# Ethernet_Interface.net
KiCad netlist of a schematic drawn in Altium Designer
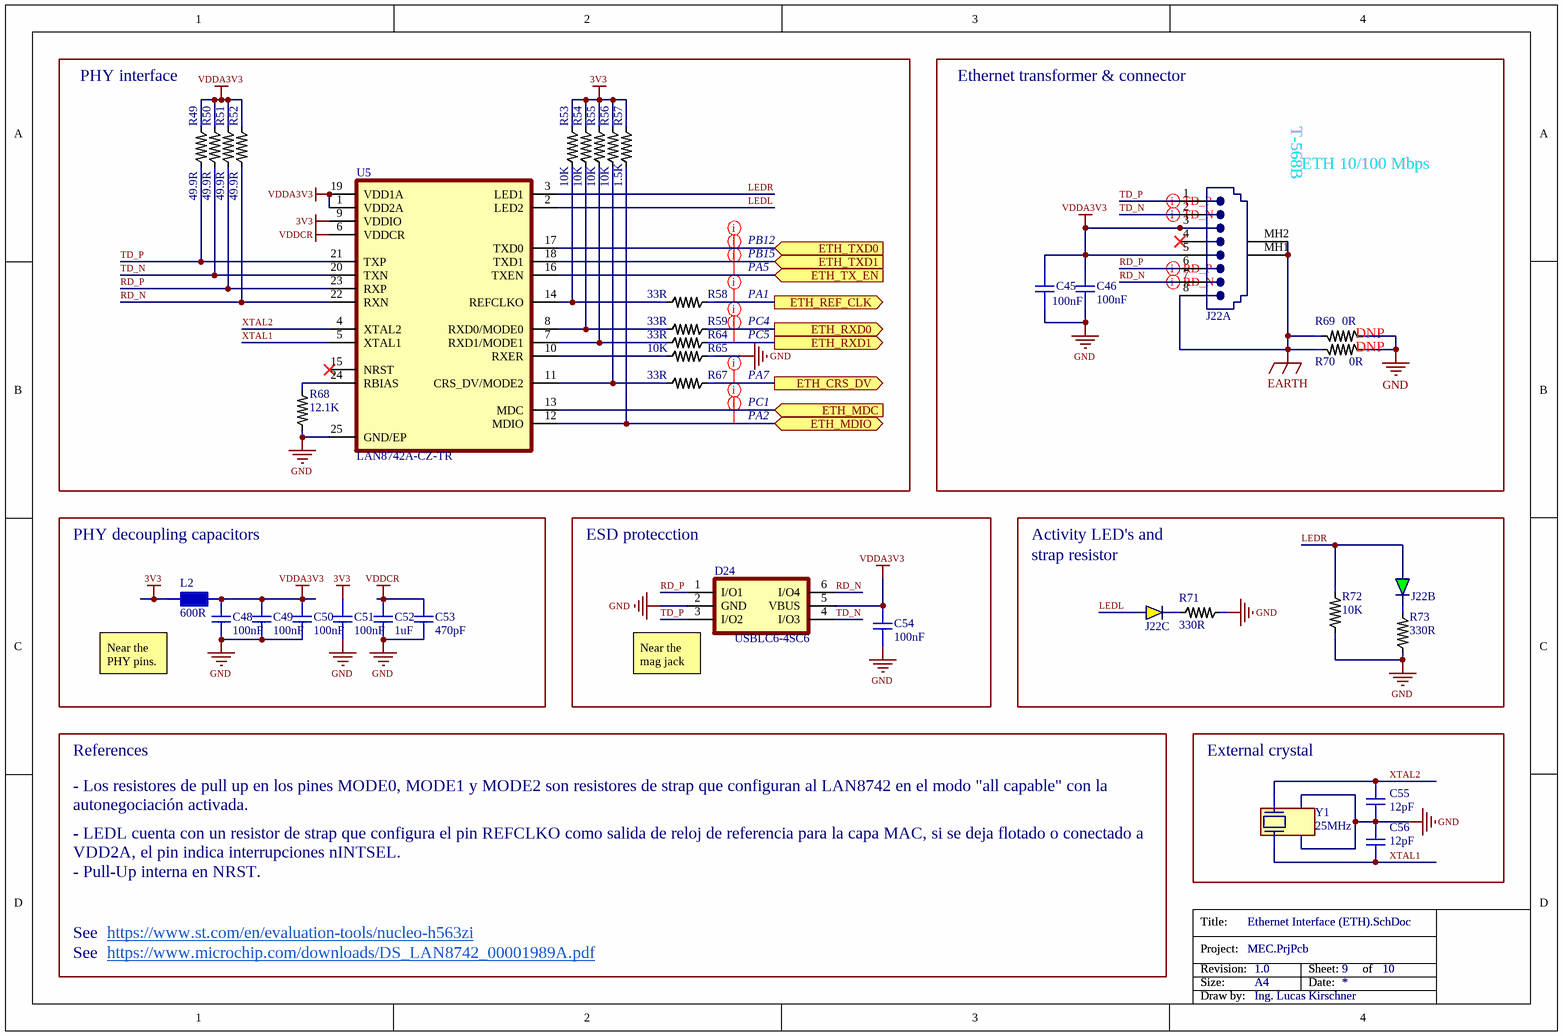
[diagram p0: Ethernet Interface (ETH).SchDoc]

(export (version "E")
  (design (tool "Eeschema 10.0.6"))
  (components
    (comp (ref "C45")
      (value "100nF")
      (footprint "CAPC1005N")
      (description "Multilayer Ceramic Capacitors MLCC - SMD/SMT 50 V 0.1uF X7R 0402 10%")
      (fields (field (name "PART NUMBER") "CC0402KRX5R9BB104") (field (name "MANUFACTURER") "YAGEO"))
      (libsource (lib "SchLib") (part "C-MLCC-100nF-50V-10%-0402"))
    )
    (comp (ref "C46")
      (value "100nF")
      (footprint "CAPC1005N")
      (description "Multilayer Ceramic Capacitors MLCC - SMD/SMT 50 V 0.1uF X7R 0402 10%")
      (fields (field (name "PART NUMBER") "CC0402KRX5R9BB104") (field (name "MANUFACTURER") "YAGEO"))
      (libsource (lib "SchLib") (part "C-MLCC-100nF-50V-10%-0402"))
    )
    (comp (ref "C48")
      (value "100nF")
      (footprint "CAPC1005N")
      (description "Multilayer Ceramic Capacitors MLCC - SMD/SMT 50 V 0.1uF X7R 0402 10%")
      (fields (field (name "PART NUMBER") "CC0402KRX5R9BB104") (field (name "MANUFACTURER") "YAGEO"))
      (libsource (lib "SchLib") (part "C-MLCC-100nF-50V-10%-0402"))
    )
    (comp (ref "C49")
      (value "100nF")
      (footprint "CAPC1005N")
      (description "Multilayer Ceramic Capacitors MLCC - SMD/SMT 50 V 0.1uF X7R 0402 10%")
      (fields (field (name "PART NUMBER") "CC0402KRX5R9BB104") (field (name "MANUFACTURER") "YAGEO"))
      (libsource (lib "SchLib") (part "C-MLCC-100nF-50V-10%-0402"))
    )
    (comp (ref "C50")
      (value "100nF")
      (footprint "CAPC1005N")
      (description "Multilayer Ceramic Capacitors MLCC - SMD/SMT 50 V 0.1uF X7R 0402 10%")
      (fields (field (name "PART NUMBER") "CC0402KRX5R9BB104") (field (name "MANUFACTURER") "YAGEO"))
      (libsource (lib "SchLib") (part "C-MLCC-100nF-50V-10%-0402"))
    )
    (comp (ref "C51")
      (value "100nF")
      (footprint "CAPC1005N")
      (description "Multilayer Ceramic Capacitors MLCC - SMD/SMT 50 V 0.1uF X7R 0402 10%")
      (fields (field (name "PART NUMBER") "CC0402KRX5R9BB104") (field (name "MANUFACTURER") "YAGEO"))
      (libsource (lib "SchLib") (part "C-MLCC-100nF-50V-10%-0402"))
    )
    (comp (ref "C52")
      (value "1uF")
      (footprint "CAPC1005N")
      (description "Multilayer Ceramic Capacitors MLCC - SMD/SMT 50V 1uF X5R 0402 10% HI CV")
      (fields (field (name "PART NUMBER") "CC0402KRX5R9BB105") (field (name "MANUFACTURER") "YAGEO"))
      (libsource (lib "SchLib") (part "C-MLCC-1uF-50V-10%-0402"))
    )
    (comp (ref "C53")
      (value "470pF")
      (footprint "CAPC1005N")
      (description "Multilayer Ceramic Capacitors MLCC - SMD/SMT 50 V 470pF X7R 0402 10%")
      (fields (field (name "PART NUMBER") "CC0402KRX7R9BB471") (field (name "MANUFACTURER") "YAGEO"))
      (libsource (lib "SchLib") (part "C-MLCC-470pF-50V-10%-0402"))
    )
    (comp (ref "C54")
      (value "100nF")
      (footprint "CAPC1005N")
      (description "Multilayer Ceramic Capacitors MLCC - SMD/SMT 50 V 0.1uF X7R 0402 10%")
      (fields (field (name "PART NUMBER") "CC0402KRX5R9BB104") (field (name "MANUFACTURER") "YAGEO"))
      (libsource (lib "SchLib") (part "C-MLCC-100nF-50V-10%-0402"))
    )
    (comp (ref "C55")
      (value "12pF")
      (footprint "CAPC1005N")
      (description "Multilayer Ceramic Capacitors MLCC - SMD/SMT 50 V 12 pF C0G 0402 1%")
      (fields (field (name "PART NUMBER") "CC0402FRNPO9BN120") (field (name "MANUFACTURER") "YAGEO"))
      (libsource (lib "SchLib") (part "C-MLCC-12pF-50V-10%-0402"))
    )
    (comp (ref "C56")
      (value "12pF")
      (footprint "CAPC1005N")
      (description "Multilayer Ceramic Capacitors MLCC - SMD/SMT 50 V 12 pF C0G 0402 1%")
      (fields (field (name "PART NUMBER") "CC0402FRNPO9BN120") (field (name "MANUFACTURER") "YAGEO"))
      (libsource (lib "SchLib") (part "C-MLCC-12pF-50V-10%-0402"))
    )
    (comp (ref "D24")
      (value "ESD Protection Diodes")
      (footprint "SOT95P280X145-6N")
      (description "ESD Protection Diodes / TVS Diodes Low Cap ESD Protect")
      (fields
        (field (name "MANUFACTURER") "STMicroelectronics")
        (field (name "MOUSER PART #") "511-USBLC6-4SC6")
        (field (name "PART NUMBER") "USBLC6-4SC6")
      )
      (libsource (lib "SchLib") (part "D-USBLC6-4SC6"))
    )
    (comp (ref "J22")
      (value "Magnetic Jack Ethernet")
      (footprint "RJ45-8P8C-VERT-THT-MAGJACK")
      (description "Modular Ethernet Connector Jack (Female) 1x1 Shielded Through Hole With LEDs With Magnetics")
      (fields (field (name "MANUFACTURER") "HANRUN") (field (name "PART NUMBER") "HY951180A"))
      (libsource (lib "") (part "J-RJ45-1P-VERT-MAGJACK-SH-LED-THT_1"))
    )
    (comp (ref "L2")
      (value "600R")
      (footprint "INDC1005N")
      (description "Ferrite Beads 600 OHM 25% Alternate Sizing Guide Below")
      (fields
        (field (name "MANUFACTURER") "Murata Electronics")
        (field (name "MOUSER PART #") "81-BLM15AX601SN1D")
      )
      (libsource (lib "SchLib") (part "L-FB-600R-100MHz-500mA-0402"))
    )
    (comp (ref "R49")
      (value "49.9R")
      (footprint "RESC1005N")
      (description "Thick Film Resistors - SMD General Purpose Chip Resistor 0402, 49.9Ohms, 1%, 1/16W")
      (fields (field (name "PART NUMBER") "RC0402FR-0749R9L") (field (name "MANUFACTURER") "YAGEO"))
      (libsource (lib "SchLib") (part "R-THICK-49R9-62.5mW-1%-0402"))
    )
    (comp (ref "R50")
      (value "49.9R")
      (footprint "RESC1005N")
      (description "Thick Film Resistors - SMD General Purpose Chip Resistor 0402, 49.9Ohms, 1%, 1/16W")
      (fields (field (name "PART NUMBER") "RC0402FR-0749R9L") (field (name "MANUFACTURER") "YAGEO"))
      (libsource (lib "SchLib") (part "R-THICK-49R9-62.5mW-1%-0402"))
    )
    (comp (ref "R51")
      (value "49.9R")
      (footprint "RESC1005N")
      (description "Thick Film Resistors - SMD General Purpose Chip Resistor 0402, 49.9Ohms, 1%, 1/16W")
      (fields (field (name "PART NUMBER") "RC0402FR-0749R9L") (field (name "MANUFACTURER") "YAGEO"))
      (libsource (lib "SchLib") (part "R-THICK-49R9-62.5mW-1%-0402"))
    )
    (comp (ref "R52")
      (value "49.9R")
      (footprint "RESC1005N")
      (description "Thick Film Resistors - SMD General Purpose Chip Resistor 0402, 49.9Ohms, 1%, 1/16W")
      (fields (field (name "PART NUMBER") "RC0402FR-0749R9L") (field (name "MANUFACTURER") "YAGEO"))
      (libsource (lib "SchLib") (part "R-THICK-49R9-62.5mW-1%-0402"))
    )
    (comp (ref "R53")
      (value "10K")
      (footprint "RESC1005N")
      (description "Thick Film Resistors - SMD General Purpose Chip Resistor 0402, 10kOhms, 1%, 1/16W")
      (fields (field (name "PART NUMBER") "RC0402FR-0710KL") (field (name "MANUFACTURER") "YAGEO"))
      (libsource (lib "SchLib") (part "R-THICK-10K-62.5mW-1%-0402"))
    )
    (comp (ref "R54")
      (value "10K")
      (footprint "RESC1005N")
      (description "Thick Film Resistors - SMD General Purpose Chip Resistor 0402, 10kOhms, 1%, 1/16W")
      (fields (field (name "PART NUMBER") "RC0402FR-0710KL") (field (name "MANUFACTURER") "YAGEO"))
      (libsource (lib "SchLib") (part "R-THICK-10K-62.5mW-1%-0402"))
    )
    (comp (ref "R55")
      (value "10K")
      (footprint "RESC1005N")
      (description "Thick Film Resistors - SMD General Purpose Chip Resistor 0402, 10kOhms, 1%, 1/16W")
      (fields (field (name "PART NUMBER") "RC0402FR-0710KL") (field (name "MANUFACTURER") "YAGEO"))
      (libsource (lib "SchLib") (part "R-THICK-10K-62.5mW-1%-0402"))
    )
    (comp (ref "R56")
      (value "10K")
      (footprint "RESC1005N")
      (description "Thick Film Resistors - SMD General Purpose Chip Resistor 0402, 10kOhms, 1%, 1/16W")
      (fields (field (name "PART NUMBER") "RC0402FR-0710KL") (field (name "MANUFACTURER") "YAGEO"))
      (libsource (lib "SchLib") (part "R-THICK-10K-62.5mW-1%-0402"))
    )
    (comp (ref "R57")
      (value "1.5K")
      (footprint "RESC1005N")
      (description "Thick Film Resistors - SMD General Purpose Chip Resistor 0402, 1.5kOhms, 1%, 1/16W")
      (fields (field (name "PART NUMBER") "RC0402FR-071K5L") (field (name "MANUFACTURER") "YAGEO"))
      (libsource (lib "SchLib") (part "R-THICK-1K5-62.5mW-1%-0402"))
    )
    (comp (ref "R58")
      (value "33R")
      (footprint "RESC1005N")
      (description "Thick Film Resistors - SMD General Purpose Chip Resistor 0402, 33Ohms, 1%, 1/16W")
      (fields (field (name "PART NUMBER") "RC0402FR-0733RL") (field (name "MANUFACTURER") "YAGEO"))
      (libsource (lib "SchLib") (part "R-THICK-33R-62.5mW-1%-0402"))
    )
    (comp (ref "R59")
      (value "33R")
      (footprint "RESC1005N")
      (description "Thick Film Resistors - SMD General Purpose Chip Resistor 0402, 33Ohms, 1%, 1/16W")
      (fields (field (name "PART NUMBER") "RC0402FR-0733RL") (field (name "MANUFACTURER") "YAGEO"))
      (libsource (lib "SchLib") (part "R-THICK-33R-62.5mW-1%-0402"))
    )
    (comp (ref "R64")
      (value "33R")
      (footprint "RESC1005N")
      (description "Thick Film Resistors - SMD General Purpose Chip Resistor 0402, 33Ohms, 1%, 1/16W")
      (fields (field (name "PART NUMBER") "RC0402FR-0733RL") (field (name "MANUFACTURER") "YAGEO"))
      (libsource (lib "SchLib") (part "R-THICK-33R-62.5mW-1%-0402"))
    )
    (comp (ref "R65")
      (value "10K")
      (footprint "RESC1005N")
      (description "Thick Film Resistors - SMD General Purpose Chip Resistor 0402, 10kOhms, 1%, 1/16W")
      (fields (field (name "PART NUMBER") "RC0402FR-0710KL") (field (name "MANUFACTURER") "YAGEO"))
      (libsource (lib "SchLib") (part "R-THICK-10K-62.5mW-1%-0402"))
    )
    (comp (ref "R67")
      (value "33R")
      (footprint "RESC1005N")
      (description "Thick Film Resistors - SMD General Purpose Chip Resistor 0402, 33Ohms, 1%, 1/16W")
      (fields (field (name "PART NUMBER") "RC0402FR-0733RL") (field (name "MANUFACTURER") "YAGEO"))
      (libsource (lib "SchLib") (part "R-THICK-33R-62.5mW-1%-0402"))
    )
    (comp (ref "R68")
      (value "12.1K")
      (footprint "RESC1005N")
      (description "Thick Film Resistors - SMD General Purpose Chip Resistor 0402, 12.1kOhms, 1%, 1/16W")
      (fields (field (name "PART NUMBER") "RC0402FR-0712K1L") (field (name "MANUFACTURER") "YAGEO"))
      (libsource (lib "SchLib") (part "R-THICK-12K1-62.5mW-1%-0402"))
    )
    (comp (ref "R69")
      (value "0R")
      (footprint "RESC1005N")
      (description "Thick Film Resistors - SMD General Purpose Chip Resistor 0402, 0Ohms, 1%, 1/16W")
      (fields (field (name "PART NUMBER") "RC0402FR-070RL") (field (name "MANUFACTURER") "YAGEO"))
      (libsource (lib "SchLib") (part "R-THICK-0R-62.5mW-1%-0402"))
    )
    (comp (ref "R70")
      (value "0R")
      (footprint "RESC1005N")
      (description "Thick Film Resistors - SMD General Purpose Chip Resistor 0402, 0Ohms, 1%, 1/16W")
      (fields (field (name "PART NUMBER") "RC0402FR-070RL") (field (name "MANUFACTURER") "YAGEO"))
      (libsource (lib "SchLib") (part "R-THICK-0R-62.5mW-1%-0402"))
    )
    (comp (ref "R71")
      (value "330R")
      (footprint "RESC1005N")
      (description "Thick Film Resistors - SMD General Purpose Chip Resistor 0402, 330Ohms, 1%, 1/16W")
      (fields (field (name "PART NUMBER") "RC0402FR-07330RL") (field (name "MANUFACTURER") "YAGEO"))
      (libsource (lib "SchLib") (part "R-THICK-330R-62.5mW-1%-0402"))
    )
    (comp (ref "R72")
      (value "10K")
      (footprint "RESC1005N")
      (description "Thick Film Resistors - SMD General Purpose Chip Resistor 0402, 10kOhms, 1%, 1/16W")
      (fields (field (name "PART NUMBER") "RC0402FR-0710KL") (field (name "MANUFACTURER") "YAGEO"))
      (libsource (lib "SchLib") (part "R-THICK-10K-62.5mW-1%-0402"))
    )
    (comp (ref "R73")
      (value "330R")
      (footprint "RESC1005N")
      (description "Thick Film Resistors - SMD General Purpose Chip Resistor 0402, 330Ohms, 1%, 1/16W")
      (fields (field (name "PART NUMBER") "RC0402FR-07330RL") (field (name "MANUFACTURER") "YAGEO"))
      (libsource (lib "SchLib") (part "R-THICK-330R-62.5mW-1%-0402"))
    )
    (comp (ref "U5")
      (value "Ethernet PHY")
      (footprint "QFN50P400X400X100-25N-D")
      (description "Ethernet PHY transceiver 10/100-Mbps")
      (fields
        (field (name "MANUFACTURER") "Microchip")
        (field (name "MOUSER PART #") "579-LAN8742A-CZ-TR")
        (field (name "PART NUMBER") "LAN8742A-CZ-TR")
      )
      (libsource (lib "SchLib") (part "U-LAN8742A"))
    )
    (comp (ref "Y1")
      (value "25MHz")
      (footprint "XTAL3225")
      (description "Crystals 25MHz 12pF 20ppm -40C +125C")
      (fields (field (name "MANUFACTURER") "ECS") (field (name "PART NUMBER") "ECS-250-12-33Q-JES-TR"))
      (libsource (lib "SchLib") (part "Y-XTAL-25MHz-12pF-20ppm-3225-SMT"))
    )
  )
  (nets
    (net (code "1") (name "/ETH_CRS_DV") (class "Default")
      (node (ref "R67") (pin "2") (pinfunction "2_2") (pintype "passive"))
    )
    (net (code "2") (name "/ETH_MDC") (class "Default")
      (node (ref "U5") (pin "13") (pinfunction "MDC_13") (pintype "passive"))
    )
    (net (code "3") (name "/ETH_MDIO") (class "Default")
      (node (ref "R57") (pin "1") (pinfunction "1_1") (pintype "passive"))
      (node (ref "U5") (pin "12") (pinfunction "MDIO_12") (pintype "passive"))
    )
    (net (code "4") (name "/ETH_REF_CLK") (class "Default")
      (node (ref "R58") (pin "2") (pinfunction "2_2") (pintype "passive"))
    )
    (net (code "5") (name "/ETH_RXD0") (class "Default")
      (node (ref "R59") (pin "2") (pinfunction "2_2") (pintype "passive"))
    )
    (net (code "6") (name "/ETH_RXD1") (class "Default")
      (node (ref "R64") (pin "2") (pinfunction "2_2") (pintype "passive"))
    )
    (net (code "7") (name "/ETH_TXD0") (class "Default")
      (node (ref "U5") (pin "17") (pinfunction "TXD0_17") (pintype "passive"))
    )
    (net (code "8") (name "/ETH_TXD1") (class "Default")
      (node (ref "U5") (pin "18") (pinfunction "TXD1_18") (pintype "passive"))
    )
    (net (code "9") (name "/ETH_TX_EN") (class "Default")
      (node (ref "U5") (pin "16") (pinfunction "TXEN_16") (pintype "passive"))
    )
    (net (code "10") (name "/LEDL") (class "Default")
      (node (ref "J22") (pin "12") (pinfunction "12_12") (pintype "passive"))
      (node (ref "U5") (pin "2") (pinfunction "LED2_2") (pintype "passive"))
    )
    (net (code "11") (name "/LEDR") (class "Default")
      (node (ref "J22") (pin "9") (pinfunction "9_9") (pintype "passive"))
      (node (ref "R72") (pin "2") (pinfunction "2_2") (pintype "passive"))
      (node (ref "U5") (pin "3") (pinfunction "LED1_3") (pintype "passive"))
    )
    (net (code "12") (name "/RD_N") (class "Default")
      (node (ref "D24") (pin "6") (pinfunction "I/O4_6") (pintype "passive"))
      (node (ref "J22") (pin "7") (pinfunction "7_7") (pintype "passive"))
      (node (ref "R52") (pin "1") (pinfunction "1_1") (pintype "passive"))
      (node (ref "U5") (pin "22") (pinfunction "RXN_22") (pintype "passive"))
    )
    (net (code "13") (name "/RD_P") (class "Default")
      (node (ref "D24") (pin "1") (pinfunction "I/O1_1") (pintype "passive"))
      (node (ref "J22") (pin "6") (pinfunction "6_6") (pintype "passive"))
      (node (ref "R51") (pin "1") (pinfunction "1_1") (pintype "passive"))
      (node (ref "U5") (pin "23") (pinfunction "RXP_23") (pintype "passive"))
    )
    (net (code "14") (name "/TD_N") (class "Default")
      (node (ref "D24") (pin "4") (pinfunction "I/O3_4") (pintype "passive"))
      (node (ref "J22") (pin "2") (pinfunction "2_2") (pintype "passive"))
      (node (ref "R50") (pin "1") (pinfunction "1_1") (pintype "passive"))
      (node (ref "U5") (pin "20") (pinfunction "TXN_20") (pintype "passive"))
    )
    (net (code "15") (name "/TD_P") (class "Default")
      (node (ref "D24") (pin "3") (pinfunction "I/O2_3") (pintype "passive"))
      (node (ref "J22") (pin "1") (pinfunction "1_1") (pintype "passive"))
      (node (ref "R49") (pin "1") (pinfunction "1_1") (pintype "passive"))
      (node (ref "U5") (pin "21") (pinfunction "TXP_21") (pintype "passive"))
    )
    (net (code "16") (name "/XTAL1") (class "Default")
      (node (ref "C56") (pin "2") (pinfunction "2_2") (pintype "passive"))
      (node (ref "U5") (pin "5") (pinfunction "XTAL1_5") (pintype "passive"))
      (node (ref "Y1") (pin "3") (pinfunction "OUT/IN_3") (pintype "passive"))
    )
    (net (code "17") (name "/XTAL2") (class "Default")
      (node (ref "C55") (pin "1") (pinfunction "1_1") (pintype "passive"))
      (node (ref "U5") (pin "4") (pinfunction "XTAL2_4") (pintype "passive"))
      (node (ref "Y1") (pin "1") (pinfunction "IN/OUT_1") (pintype "passive"))
    )
    (net (code "18") (name "3V3") (class "Default")
      (node (ref "C51") (pin "1") (pinfunction "1_1") (pintype "passive"))
      (node (ref "L2") (pin "1") (pinfunction "1_1") (pintype "passive"))
      (node (ref "R53") (pin "2") (pinfunction "2_2") (pintype "passive"))
      (node (ref "R54") (pin "2") (pinfunction "2_2") (pintype "passive"))
      (node (ref "R55") (pin "2") (pinfunction "2_2") (pintype "passive"))
      (node (ref "R56") (pin "2") (pinfunction "2_2") (pintype "passive"))
      (node (ref "R57") (pin "2") (pinfunction "2_2") (pintype "passive"))
      (node (ref "U5") (pin "9") (pinfunction "VDDIO_9") (pintype "passive"))
    )
    (net (code "19") (name "EARTH") (class "Default")
      (node (ref "J22") (pin "8") (pinfunction "8_8") (pintype "passive"))
      (node (ref "J22") (pin "MH1") (pinfunction "MH1_MH1") (pintype "passive"))
      (node (ref "J22") (pin "MH2") (pinfunction "MH2_MH2") (pintype "passive"))
      (node (ref "R69") (pin "2") (pinfunction "2_2") (pintype "passive"))
      (node (ref "R70") (pin "2") (pinfunction "2_2") (pintype "passive"))
    )
    (net (code "20") (name "GND") (class "Default")
      (node (ref "C45") (pin "2") (pinfunction "2_2") (pintype "passive"))
      (node (ref "C46") (pin "2") (pinfunction "2_2") (pintype "passive"))
      (node (ref "C48") (pin "2") (pinfunction "2_2") (pintype "passive"))
      (node (ref "C49") (pin "2") (pinfunction "2_2") (pintype "passive"))
      (node (ref "C50") (pin "2") (pinfunction "2_2") (pintype "passive"))
      (node (ref "C51") (pin "2") (pinfunction "2_2") (pintype "passive"))
      (node (ref "C52") (pin "2") (pinfunction "2_2") (pintype "passive"))
      (node (ref "C53") (pin "2") (pinfunction "2_2") (pintype "passive"))
      (node (ref "C54") (pin "2") (pinfunction "2_2") (pintype "passive"))
      (node (ref "C55") (pin "2") (pinfunction "2_2") (pintype "passive"))
      (node (ref "C56") (pin "1") (pinfunction "1_1") (pintype "passive"))
      (node (ref "D24") (pin "2") (pinfunction "GND_2") (pintype "passive"))
      (node (ref "R65") (pin "2") (pinfunction "2_2") (pintype "passive"))
      (node (ref "R68") (pin "1") (pinfunction "1_1") (pintype "passive"))
      (node (ref "R69") (pin "1") (pinfunction "1_1") (pintype "passive"))
      (node (ref "R70") (pin "1") (pinfunction "1_1") (pintype "passive"))
      (node (ref "R71") (pin "2") (pinfunction "2_2") (pintype "passive"))
      (node (ref "R72") (pin "1") (pinfunction "1_1") (pintype "passive"))
      (node (ref "R73") (pin "1") (pinfunction "1_1") (pintype "passive"))
      (node (ref "U5") (pin "25") (pinfunction "GND/EP_25") (pintype "passive"))
      (node (ref "Y1") (pin "2") (pinfunction "GND_2") (pintype "passive"))
      (node (ref "Y1") (pin "4") (pinfunction "GND_4") (pintype "passive"))
    )
    (net (code "21") (name "Net-(J22-Pad10)") (class "Default")
      (node (ref "J22") (pin "10") (pinfunction "10_10") (pintype "passive"))
      (node (ref "R73") (pin "2") (pinfunction "2_2") (pintype "passive"))
    )
    (net (code "22") (name "Net-(J22-Pad11)") (class "Default")
      (node (ref "J22") (pin "11") (pinfunction "11_11") (pintype "passive"))
      (node (ref "R71") (pin "1") (pinfunction "1_1") (pintype "passive"))
    )
    (net (code "23") (name "Net-(U5-CRS_DV{slash}MODE2)") (class "Default")
      (node (ref "R56") (pin "1") (pinfunction "1_1") (pintype "passive"))
      (node (ref "R67") (pin "1") (pinfunction "1_1") (pintype "passive"))
      (node (ref "U5") (pin "11") (pinfunction "CRS_DV/MODE2_11") (pintype "passive"))
    )
    (net (code "24") (name "Net-(U5-RBIAS)") (class "Default")
      (node (ref "R68") (pin "2") (pinfunction "2_2") (pintype "passive"))
      (node (ref "U5") (pin "24") (pinfunction "RBIAS_24") (pintype "passive"))
    )
    (net (code "25") (name "Net-(U5-REFCLKO)") (class "Default")
      (node (ref "R53") (pin "1") (pinfunction "1_1") (pintype "passive"))
      (node (ref "R58") (pin "1") (pinfunction "1_1") (pintype "passive"))
      (node (ref "U5") (pin "14") (pinfunction "REFCLKO_14") (pintype "passive"))
    )
    (net (code "26") (name "Net-(U5-RXD0{slash}MODE0)") (class "Default")
      (node (ref "R54") (pin "1") (pinfunction "1_1") (pintype "passive"))
      (node (ref "R59") (pin "1") (pinfunction "1_1") (pintype "passive"))
      (node (ref "U5") (pin "8") (pinfunction "RXD0/MODE0_8") (pintype "passive"))
    )
    (net (code "27") (name "Net-(U5-RXD1{slash}MODE1)") (class "Default")
      (node (ref "R55") (pin "1") (pinfunction "1_1") (pintype "passive"))
      (node (ref "R64") (pin "1") (pinfunction "1_1") (pintype "passive"))
      (node (ref "U5") (pin "7") (pinfunction "RXD1/MODE1_7") (pintype "passive"))
    )
    (net (code "28") (name "Net-(U5-RXER)") (class "Default")
      (node (ref "R65") (pin "1") (pinfunction "1_1") (pintype "passive"))
      (node (ref "U5") (pin "10") (pinfunction "RXER_10") (pintype "passive"))
    )
    (net (code "29") (name "VDDA3V3") (class "Default")
      (node (ref "C45") (pin "1") (pinfunction "1_1") (pintype "passive"))
      (node (ref "C46") (pin "1") (pinfunction "1_1") (pintype "passive"))
      (node (ref "C48") (pin "1") (pinfunction "1_1") (pintype "passive"))
      (node (ref "C49") (pin "1") (pinfunction "1_1") (pintype "passive"))
      (node (ref "C50") (pin "1") (pinfunction "1_1") (pintype "passive"))
      (node (ref "C54") (pin "1") (pinfunction "1_1") (pintype "passive"))
      (node (ref "D24") (pin "5") (pinfunction "VBUS_5") (pintype "passive"))
      (node (ref "J22") (pin "3") (pinfunction "3_3") (pintype "passive"))
      (node (ref "J22") (pin "5") (pinfunction "5_5") (pintype "passive"))
      (node (ref "L2") (pin "2") (pinfunction "2_2") (pintype "passive"))
      (node (ref "R49") (pin "2") (pinfunction "2_2") (pintype "passive"))
      (node (ref "R50") (pin "2") (pinfunction "2_2") (pintype "passive"))
      (node (ref "R51") (pin "2") (pinfunction "2_2") (pintype "passive"))
      (node (ref "R52") (pin "2") (pinfunction "2_2") (pintype "passive"))
      (node (ref "U5") (pin "1") (pinfunction "VDD2A_1") (pintype "passive"))
      (node (ref "U5") (pin "19") (pinfunction "VDD1A_19") (pintype "passive"))
    )
    (net (code "30") (name "VDDCR") (class "Default")
      (node (ref "C52") (pin "1") (pinfunction "1_1") (pintype "passive"))
      (node (ref "C53") (pin "1") (pinfunction "1_1") (pintype "passive"))
      (node (ref "U5") (pin "6") (pinfunction "VDDCR_6") (pintype "passive"))
    )
    (net (code "31") (name "unconnected-(J22-Pad4)") (class "Default")
      (node (ref "J22") (pin "4") (pinfunction "4_4") (pintype "passive+no_connect"))
    )
    (net (code "32") (name "unconnected-(U5-NRST-Pad15)") (class "Default")
      (node (ref "U5") (pin "15") (pinfunction "NRST_15") (pintype "passive+no_connect"))
    )
  )
)
